# motor_shield__SD_v1_1_-_Ryan.net
KiCad netlist of a schematic drawn in EAGLE
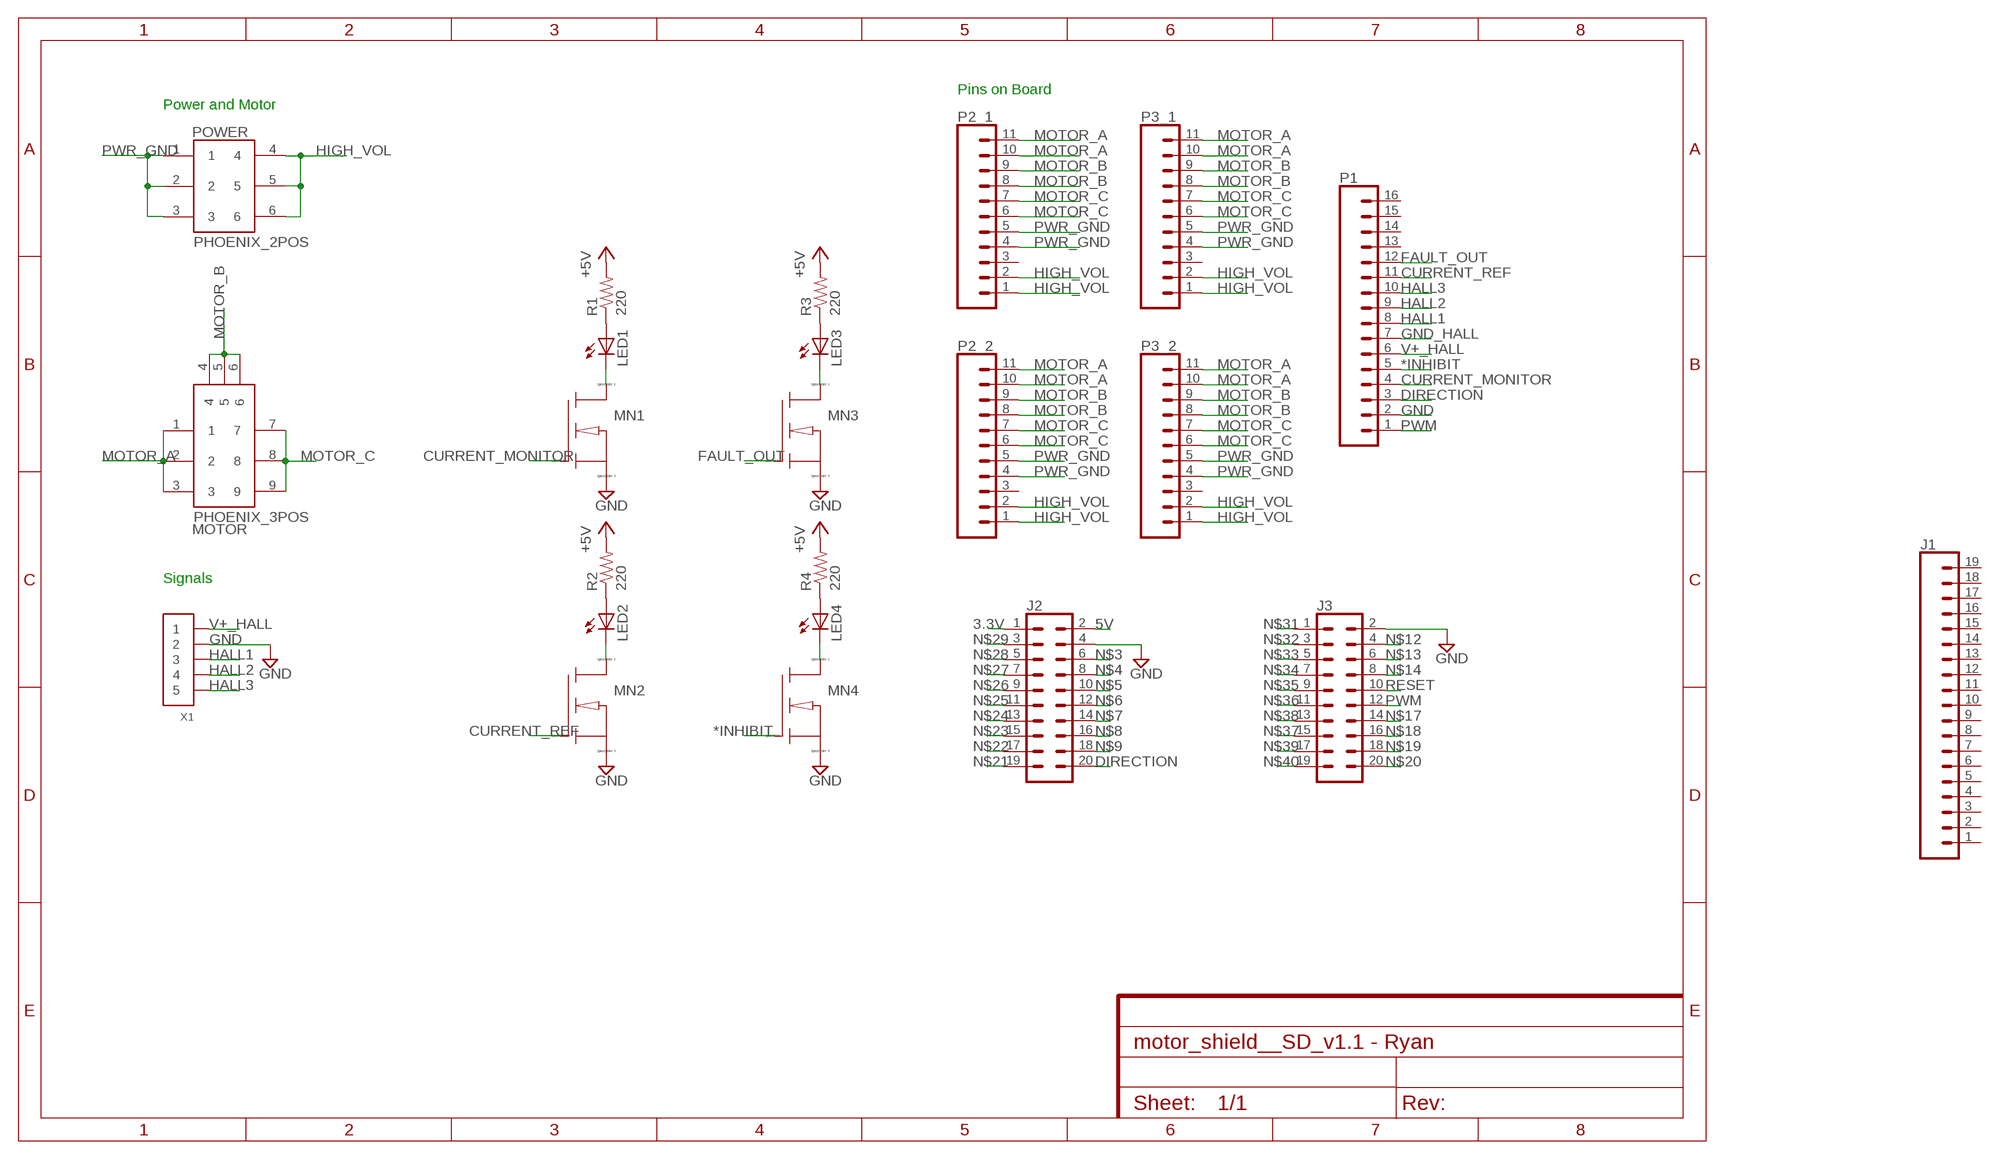
[diagram p0: schematic, sheet 1]

(export (version "E")
  (design (tool "Eeschema 10.0.6"))
  (components
    (comp (ref "J1")
      (value "CONN_19")
      (footprint "eagle-import:1X19")
      (libsource (lib "eagle-import") (part "CONN_19"))
    )
    (comp (ref "J2")
      (value "CONN_10X2")
      (footprint "eagle-import:2X10")
      (libsource (lib "eagle-import") (part "CONN_10X2"))
    )
    (comp (ref "J3")
      (value "CONN_10X2")
      (footprint "eagle-import:2X10")
      (libsource (lib "eagle-import") (part "CONN_10X2"))
    )
    (comp (ref "LED1")
      (value "LEDCHIPLED_0805")
      (footprint "eagle-import:CHIPLED_0805")
      (libsource (lib "eagle-import") (part "LEDCHIPLED_0805"))
    )
    (comp (ref "LED2")
      (value "LEDCHIPLED_0805")
      (footprint "eagle-import:CHIPLED_0805")
      (libsource (lib "eagle-import") (part "LEDCHIPLED_0805"))
    )
    (comp (ref "LED3")
      (value "LEDCHIPLED_0805")
      (footprint "eagle-import:CHIPLED_0805")
      (libsource (lib "eagle-import") (part "LEDCHIPLED_0805"))
    )
    (comp (ref "LED4")
      (value "LEDCHIPLED_0805")
      (footprint "eagle-import:CHIPLED_0805")
      (libsource (lib "eagle-import") (part "LEDCHIPLED_0805"))
    )
    (comp (ref "MN1")
      (value "NMOS")
      (footprint "eagle-import:SOT23")
      (libsource (lib "eagle-import") (part "NMOS"))
    )
    (comp (ref "MN2")
      (value "NMOS")
      (footprint "eagle-import:SOT23")
      (libsource (lib "eagle-import") (part "NMOS"))
    )
    (comp (ref "MN3")
      (value "NMOS")
      (footprint "eagle-import:SOT23")
      (libsource (lib "eagle-import") (part "NMOS"))
    )
    (comp (ref "MN4")
      (value "NMOS")
      (footprint "eagle-import:SOT23")
      (libsource (lib "eagle-import") (part "NMOS"))
    )
    (comp (ref "MOTOR")
      (value "PHOENIX_3POS")
      (footprint "eagle-import:PHOENIX_3POS")
      (libsource (lib "eagle-import") (part "PHOENIX_3POS"))
    )
    (comp (ref "P1")
      (value "CONN_16LOCK")
      (footprint "eagle-import:1X16_LOCK")
      (libsource (lib "eagle-import") (part "CONN_16LOCK"))
    )
    (comp (ref "P2_1")
      (value "CONN_11")
      (footprint "eagle-import:1X11")
      (libsource (lib "eagle-import") (part "CONN_11"))
    )
    (comp (ref "P2_2")
      (value "CONN_11")
      (footprint "eagle-import:1X11")
      (libsource (lib "eagle-import") (part "CONN_11"))
    )
    (comp (ref "P3_1")
      (value "CONN_11")
      (footprint "eagle-import:1X11")
      (libsource (lib "eagle-import") (part "CONN_11"))
    )
    (comp (ref "P3_2")
      (value "CONN_11")
      (footprint "eagle-import:1X11")
      (libsource (lib "eagle-import") (part "CONN_11"))
    )
    (comp (ref "POWER")
      (value "PHOENIX_2POS")
      (footprint "eagle-import:PHOENIX_2POS")
      (libsource (lib "eagle-import") (part "PHOENIX_2POS"))
    )
    (comp (ref "R1")
      (value "220")
      (footprint "eagle-import:R0603")
      (libsource (lib "eagle-import") (part "R-US_R0603"))
    )
    (comp (ref "R2")
      (value "220")
      (footprint "eagle-import:R0603")
      (libsource (lib "eagle-import") (part "R-US_R0603"))
    )
    (comp (ref "R3")
      (value "220")
      (footprint "eagle-import:R0603")
      (libsource (lib "eagle-import") (part "R-US_R0603"))
    )
    (comp (ref "R4")
      (value "220")
      (footprint "eagle-import:R0603")
      (libsource (lib "eagle-import") (part "R-US_R0603"))
    )
    (comp (ref "X1")
      (value "CONN_5-1-53261")
      (footprint "eagle-import:PB-53261-05")
      (libsource (lib "eagle-import") (part "CONN_5-1-53261"))
    )
  )
  (nets
    (net (code "1") (name "+5V") (class "Default")
      (node (ref "R1") (pin "2") (pinfunction "2_2") (pintype "passive"))
      (node (ref "R2") (pin "2") (pinfunction "2_2") (pintype "passive"))
      (node (ref "R3") (pin "2") (pinfunction "2_2") (pintype "passive"))
      (node (ref "R4") (pin "2") (pinfunction "2_2") (pintype "passive"))
    )
    (net (code "2") (name "/*INHIBIT") (class "Default")
      (node (ref "MN4") (pin "1") (pinfunction "G_1") (pintype "passive"))
      (node (ref "P1") (pin "5") (pinfunction "5_5") (pintype "passive"))
    )
    (net (code "3") (name "/3.3V") (class "Default")
      (node (ref "J2") (pin "1") (pinfunction "1_1") (pintype "passive"))
    )
    (net (code "4") (name "/5V") (class "Default")
      (node (ref "J2") (pin "2") (pinfunction "2_2") (pintype "passive"))
    )
    (net (code "5") (name "/CURRENT_MONITOR") (class "Default")
      (node (ref "MN1") (pin "1") (pinfunction "G_1") (pintype "passive"))
      (node (ref "P1") (pin "4") (pinfunction "4_4") (pintype "passive"))
    )
    (net (code "6") (name "/CURRENT_REF") (class "Default")
      (node (ref "MN2") (pin "1") (pinfunction "G_1") (pintype "passive"))
      (node (ref "P1") (pin "11") (pinfunction "11_11") (pintype "passive"))
    )
    (net (code "7") (name "/DIRECTION") (class "Default")
      (node (ref "J2") (pin "20") (pinfunction "20_20") (pintype "passive"))
      (node (ref "P1") (pin "3") (pinfunction "3_3") (pintype "passive"))
    )
    (net (code "8") (name "/FAULT_OUT") (class "Default")
      (node (ref "MN3") (pin "1") (pinfunction "G_1") (pintype "passive"))
      (node (ref "P1") (pin "12") (pinfunction "12_12") (pintype "passive"))
    )
    (net (code "9") (name "/GND_HALL") (class "Default")
      (node (ref "P1") (pin "7") (pinfunction "7_7") (pintype "passive"))
    )
    (net (code "10") (name "/HALL1") (class "Default")
      (node (ref "P1") (pin "8") (pinfunction "8_8") (pintype "passive"))
      (node (ref "X1") (pin "3") (pinfunction "3_3") (pintype "bidirectional"))
    )
    (net (code "11") (name "/HALL2") (class "Default")
      (node (ref "P1") (pin "9") (pinfunction "9_9") (pintype "passive"))
      (node (ref "X1") (pin "4") (pinfunction "4_4") (pintype "bidirectional"))
    )
    (net (code "12") (name "/HALL3") (class "Default")
      (node (ref "P1") (pin "10") (pinfunction "10_10") (pintype "passive"))
      (node (ref "X1") (pin "5") (pinfunction "5_5") (pintype "bidirectional"))
    )
    (net (code "13") (name "/HIGH_VOL") (class "Default")
      (node (ref "P2_1") (pin "1") (pinfunction "1_1") (pintype "passive"))
      (node (ref "P2_1") (pin "2") (pinfunction "2_2") (pintype "passive"))
      (node (ref "P2_2") (pin "1") (pinfunction "1_1") (pintype "passive"))
      (node (ref "P2_2") (pin "2") (pinfunction "2_2") (pintype "passive"))
      (node (ref "P3_1") (pin "1") (pinfunction "1_1") (pintype "passive"))
      (node (ref "P3_1") (pin "2") (pinfunction "2_2") (pintype "passive"))
      (node (ref "P3_2") (pin "1") (pinfunction "1_1") (pintype "passive"))
      (node (ref "P3_2") (pin "2") (pinfunction "2_2") (pintype "passive"))
      (node (ref "POWER") (pin "4") (pinfunction "4_4") (pintype "bidirectional"))
      (node (ref "POWER") (pin "5") (pinfunction "5_5") (pintype "bidirectional"))
      (node (ref "POWER") (pin "6") (pinfunction "6_6") (pintype "bidirectional"))
    )
    (net (code "14") (name "/MOTOR_A") (class "Default")
      (node (ref "MOTOR") (pin "1") (pinfunction "1_1") (pintype "bidirectional"))
      (node (ref "MOTOR") (pin "2") (pinfunction "2_2") (pintype "bidirectional"))
      (node (ref "MOTOR") (pin "3") (pinfunction "3_3") (pintype "bidirectional"))
      (node (ref "P2_1") (pin "10") (pinfunction "10_10") (pintype "passive"))
      (node (ref "P2_1") (pin "11") (pinfunction "11_11") (pintype "passive"))
      (node (ref "P2_2") (pin "10") (pinfunction "10_10") (pintype "passive"))
      (node (ref "P2_2") (pin "11") (pinfunction "11_11") (pintype "passive"))
      (node (ref "P3_1") (pin "10") (pinfunction "10_10") (pintype "passive"))
      (node (ref "P3_1") (pin "11") (pinfunction "11_11") (pintype "passive"))
      (node (ref "P3_2") (pin "10") (pinfunction "10_10") (pintype "passive"))
      (node (ref "P3_2") (pin "11") (pinfunction "11_11") (pintype "passive"))
    )
    (net (code "15") (name "/MOTOR_B") (class "Default")
      (node (ref "MOTOR") (pin "4") (pinfunction "4_4") (pintype "bidirectional"))
      (node (ref "MOTOR") (pin "5") (pinfunction "5_5") (pintype "bidirectional"))
      (node (ref "MOTOR") (pin "6") (pinfunction "6_6") (pintype "bidirectional"))
      (node (ref "P2_1") (pin "8") (pinfunction "8_8") (pintype "passive"))
      (node (ref "P2_1") (pin "9") (pinfunction "9_9") (pintype "passive"))
      (node (ref "P2_2") (pin "8") (pinfunction "8_8") (pintype "passive"))
      (node (ref "P2_2") (pin "9") (pinfunction "9_9") (pintype "passive"))
      (node (ref "P3_1") (pin "8") (pinfunction "8_8") (pintype "passive"))
      (node (ref "P3_1") (pin "9") (pinfunction "9_9") (pintype "passive"))
      (node (ref "P3_2") (pin "8") (pinfunction "8_8") (pintype "passive"))
      (node (ref "P3_2") (pin "9") (pinfunction "9_9") (pintype "passive"))
    )
    (net (code "16") (name "/MOTOR_C") (class "Default")
      (node (ref "MOTOR") (pin "7") (pinfunction "7_7") (pintype "bidirectional"))
      (node (ref "MOTOR") (pin "8") (pinfunction "8_8") (pintype "bidirectional"))
      (node (ref "MOTOR") (pin "9") (pinfunction "9_9") (pintype "bidirectional"))
      (node (ref "P2_1") (pin "6") (pinfunction "6_6") (pintype "passive"))
      (node (ref "P2_1") (pin "7") (pinfunction "7_7") (pintype "passive"))
      (node (ref "P2_2") (pin "6") (pinfunction "6_6") (pintype "passive"))
      (node (ref "P2_2") (pin "7") (pinfunction "7_7") (pintype "passive"))
      (node (ref "P3_1") (pin "6") (pinfunction "6_6") (pintype "passive"))
      (node (ref "P3_1") (pin "7") (pinfunction "7_7") (pintype "passive"))
      (node (ref "P3_2") (pin "6") (pinfunction "6_6") (pintype "passive"))
      (node (ref "P3_2") (pin "7") (pinfunction "7_7") (pintype "passive"))
    )
    (net (code "17") (name "/N$3") (class "Default")
      (node (ref "J2") (pin "6") (pinfunction "6_6") (pintype "passive"))
    )
    (net (code "18") (name "/N$4") (class "Default")
      (node (ref "J2") (pin "8") (pinfunction "8_8") (pintype "passive"))
    )
    (net (code "19") (name "/N$5") (class "Default")
      (node (ref "J2") (pin "10") (pinfunction "10_10") (pintype "passive"))
    )
    (net (code "20") (name "/N$6") (class "Default")
      (node (ref "J2") (pin "12") (pinfunction "12_12") (pintype "passive"))
    )
    (net (code "21") (name "/N$7") (class "Default")
      (node (ref "J2") (pin "14") (pinfunction "14_14") (pintype "passive"))
    )
    (net (code "22") (name "/N$8") (class "Default")
      (node (ref "J2") (pin "16") (pinfunction "16_16") (pintype "passive"))
    )
    (net (code "23") (name "/N$9") (class "Default")
      (node (ref "J2") (pin "18") (pinfunction "18_18") (pintype "passive"))
    )
    (net (code "24") (name "/N$12") (class "Default")
      (node (ref "J3") (pin "4") (pinfunction "4_4") (pintype "passive"))
    )
    (net (code "25") (name "/N$13") (class "Default")
      (node (ref "J3") (pin "6") (pinfunction "6_6") (pintype "passive"))
    )
    (net (code "26") (name "/N$14") (class "Default")
      (node (ref "J3") (pin "8") (pinfunction "8_8") (pintype "passive"))
    )
    (net (code "27") (name "/N$17") (class "Default")
      (node (ref "J3") (pin "14") (pinfunction "14_14") (pintype "passive"))
    )
    (net (code "28") (name "/N$18") (class "Default")
      (node (ref "J3") (pin "16") (pinfunction "16_16") (pintype "passive"))
    )
    (net (code "29") (name "/N$19") (class "Default")
      (node (ref "J3") (pin "18") (pinfunction "18_18") (pintype "passive"))
    )
    (net (code "30") (name "/N$20") (class "Default")
      (node (ref "J3") (pin "20") (pinfunction "20_20") (pintype "passive"))
    )
    (net (code "31") (name "/N$21") (class "Default")
      (node (ref "J2") (pin "19") (pinfunction "19_19") (pintype "passive"))
    )
    (net (code "32") (name "/N$22") (class "Default")
      (node (ref "J2") (pin "17") (pinfunction "17_17") (pintype "passive"))
    )
    (net (code "33") (name "/N$23") (class "Default")
      (node (ref "J2") (pin "15") (pinfunction "15_15") (pintype "passive"))
    )
    (net (code "34") (name "/N$24") (class "Default")
      (node (ref "J2") (pin "13") (pinfunction "13_13") (pintype "passive"))
    )
    (net (code "35") (name "/N$25") (class "Default")
      (node (ref "J2") (pin "11") (pinfunction "11_11") (pintype "passive"))
    )
    (net (code "36") (name "/N$26") (class "Default")
      (node (ref "J2") (pin "9") (pinfunction "9_9") (pintype "passive"))
    )
    (net (code "37") (name "/N$27") (class "Default")
      (node (ref "J2") (pin "7") (pinfunction "7_7") (pintype "passive"))
    )
    (net (code "38") (name "/N$28") (class "Default")
      (node (ref "J2") (pin "5") (pinfunction "5_5") (pintype "passive"))
    )
    (net (code "39") (name "/N$29") (class "Default")
      (node (ref "J2") (pin "3") (pinfunction "3_3") (pintype "passive"))
    )
    (net (code "40") (name "/N$31") (class "Default")
      (node (ref "J3") (pin "1") (pinfunction "1_1") (pintype "passive"))
    )
    (net (code "41") (name "/N$32") (class "Default")
      (node (ref "J3") (pin "3") (pinfunction "3_3") (pintype "passive"))
    )
    (net (code "42") (name "/N$33") (class "Default")
      (node (ref "J3") (pin "5") (pinfunction "5_5") (pintype "passive"))
    )
    (net (code "43") (name "/N$34") (class "Default")
      (node (ref "J3") (pin "7") (pinfunction "7_7") (pintype "passive"))
    )
    (net (code "44") (name "/N$35") (class "Default")
      (node (ref "J3") (pin "9") (pinfunction "9_9") (pintype "passive"))
    )
    (net (code "45") (name "/N$36") (class "Default")
      (node (ref "J3") (pin "11") (pinfunction "11_11") (pintype "passive"))
    )
    (net (code "46") (name "/N$37") (class "Default")
      (node (ref "J3") (pin "15") (pinfunction "15_15") (pintype "passive"))
    )
    (net (code "47") (name "/N$38") (class "Default")
      (node (ref "J3") (pin "13") (pinfunction "13_13") (pintype "passive"))
    )
    (net (code "48") (name "/N$39") (class "Default")
      (node (ref "J3") (pin "17") (pinfunction "17_17") (pintype "passive"))
    )
    (net (code "49") (name "/N$40") (class "Default")
      (node (ref "J3") (pin "19") (pinfunction "19_19") (pintype "passive"))
    )
    (net (code "50") (name "/PWM") (class "Default")
      (node (ref "J3") (pin "12") (pinfunction "12_12") (pintype "passive"))
      (node (ref "P1") (pin "1") (pinfunction "1_1") (pintype "passive"))
    )
    (net (code "51") (name "/PWR_GND") (class "Default")
      (node (ref "P2_1") (pin "4") (pinfunction "4_4") (pintype "passive"))
      (node (ref "P2_1") (pin "5") (pinfunction "5_5") (pintype "passive"))
      (node (ref "P2_2") (pin "4") (pinfunction "4_4") (pintype "passive"))
      (node (ref "P2_2") (pin "5") (pinfunction "5_5") (pintype "passive"))
      (node (ref "P3_1") (pin "4") (pinfunction "4_4") (pintype "passive"))
      (node (ref "P3_1") (pin "5") (pinfunction "5_5") (pintype "passive"))
      (node (ref "P3_2") (pin "4") (pinfunction "4_4") (pintype "passive"))
      (node (ref "P3_2") (pin "5") (pinfunction "5_5") (pintype "passive"))
      (node (ref "POWER") (pin "1") (pinfunction "1_1") (pintype "bidirectional"))
      (node (ref "POWER") (pin "2") (pinfunction "2_2") (pintype "bidirectional"))
      (node (ref "POWER") (pin "3") (pinfunction "3_3") (pintype "bidirectional"))
    )
    (net (code "52") (name "/RESET") (class "Default")
      (node (ref "J3") (pin "10") (pinfunction "10_10") (pintype "passive"))
    )
    (net (code "53") (name "/V+_HALL") (class "Default")
      (node (ref "P1") (pin "6") (pinfunction "6_6") (pintype "passive"))
      (node (ref "X1") (pin "1") (pinfunction "1_1") (pintype "bidirectional"))
    )
    (net (code "54") (name "GND") (class "Default")
      (node (ref "J2") (pin "4") (pinfunction "4_4") (pintype "passive"))
      (node (ref "J3") (pin "2") (pinfunction "2_2") (pintype "passive"))
      (node (ref "MN1") (pin "2") (pinfunction "S_2") (pintype "passive"))
      (node (ref "MN2") (pin "2") (pinfunction "S_2") (pintype "passive"))
      (node (ref "MN3") (pin "2") (pinfunction "S_2") (pintype "passive"))
      (node (ref "MN4") (pin "2") (pinfunction "S_2") (pintype "passive"))
      (node (ref "P1") (pin "2") (pinfunction "2_2") (pintype "passive"))
      (node (ref "X1") (pin "2") (pinfunction "2_2") (pintype "bidirectional"))
    )
    (net (code "55") (name "Net-(LED1-PadA)") (class "Default")
      (node (ref "LED1") (pin "A") (pinfunction "A_A") (pintype "passive"))
      (node (ref "R1") (pin "1") (pinfunction "1_1") (pintype "passive"))
    )
    (net (code "56") (name "Net-(LED2-PadA)") (class "Default")
      (node (ref "LED2") (pin "A") (pinfunction "A_A") (pintype "passive"))
      (node (ref "R2") (pin "1") (pinfunction "1_1") (pintype "passive"))
    )
    (net (code "57") (name "Net-(LED3-PadA)") (class "Default")
      (node (ref "LED3") (pin "A") (pinfunction "A_A") (pintype "passive"))
      (node (ref "R3") (pin "1") (pinfunction "1_1") (pintype "passive"))
    )
    (net (code "58") (name "Net-(LED4-PadA)") (class "Default")
      (node (ref "LED4") (pin "A") (pinfunction "A_A") (pintype "passive"))
      (node (ref "R4") (pin "1") (pinfunction "1_1") (pintype "passive"))
    )
    (net (code "59") (name "Net-(MN1-D)") (class "Default")
      (node (ref "LED1") (pin "C") (pinfunction "C_C") (pintype "passive"))
      (node (ref "MN1") (pin "3") (pinfunction "D_3") (pintype "passive"))
    )
    (net (code "60") (name "Net-(MN2-D)") (class "Default")
      (node (ref "LED2") (pin "C") (pinfunction "C_C") (pintype "passive"))
      (node (ref "MN2") (pin "3") (pinfunction "D_3") (pintype "passive"))
    )
    (net (code "61") (name "Net-(MN3-D)") (class "Default")
      (node (ref "LED3") (pin "C") (pinfunction "C_C") (pintype "passive"))
      (node (ref "MN3") (pin "3") (pinfunction "D_3") (pintype "passive"))
    )
    (net (code "62") (name "Net-(MN4-D)") (class "Default")
      (node (ref "LED4") (pin "C") (pinfunction "C_C") (pintype "passive"))
      (node (ref "MN4") (pin "3") (pinfunction "D_3") (pintype "passive"))
    )
    (net (code "63") (name "unconnected-(J1-Pad1)") (class "Default")
      (node (ref "J1") (pin "1") (pinfunction "1_1") (pintype "passive"))
    )
    (net (code "64") (name "unconnected-(J1-Pad2)") (class "Default")
      (node (ref "J1") (pin "2") (pinfunction "2_2") (pintype "passive"))
    )
    (net (code "65") (name "unconnected-(J1-Pad3)") (class "Default")
      (node (ref "J1") (pin "3") (pinfunction "3_3") (pintype "passive"))
    )
    (net (code "66") (name "unconnected-(J1-Pad4)") (class "Default")
      (node (ref "J1") (pin "4") (pinfunction "4_4") (pintype "passive"))
    )
    (net (code "67") (name "unconnected-(J1-Pad5)") (class "Default")
      (node (ref "J1") (pin "5") (pinfunction "5_5") (pintype "passive"))
    )
    (net (code "68") (name "unconnected-(J1-Pad6)") (class "Default")
      (node (ref "J1") (pin "6") (pinfunction "6_6") (pintype "passive"))
    )
    (net (code "69") (name "unconnected-(J1-Pad7)") (class "Default")
      (node (ref "J1") (pin "7") (pinfunction "7_7") (pintype "passive"))
    )
    (net (code "70") (name "unconnected-(J1-Pad8)") (class "Default")
      (node (ref "J1") (pin "8") (pinfunction "8_8") (pintype "passive"))
    )
    (net (code "71") (name "unconnected-(J1-Pad9)") (class "Default")
      (node (ref "J1") (pin "9") (pinfunction "9_9") (pintype "passive"))
    )
    (net (code "72") (name "unconnected-(J1-Pad10)") (class "Default")
      (node (ref "J1") (pin "10") (pinfunction "10_10") (pintype "passive"))
    )
    (net (code "73") (name "unconnected-(J1-Pad11)") (class "Default")
      (node (ref "J1") (pin "11") (pinfunction "11_11") (pintype "passive"))
    )
    (net (code "74") (name "unconnected-(J1-Pad12)") (class "Default")
      (node (ref "J1") (pin "12") (pinfunction "12_12") (pintype "passive"))
    )
    (net (code "75") (name "unconnected-(J1-Pad13)") (class "Default")
      (node (ref "J1") (pin "13") (pinfunction "13_13") (pintype "passive"))
    )
    (net (code "76") (name "unconnected-(J1-Pad14)") (class "Default")
      (node (ref "J1") (pin "14") (pinfunction "14_14") (pintype "passive"))
    )
    (net (code "77") (name "unconnected-(J1-Pad15)") (class "Default")
      (node (ref "J1") (pin "15") (pinfunction "15_15") (pintype "passive"))
    )
    (net (code "78") (name "unconnected-(J1-Pad16)") (class "Default")
      (node (ref "J1") (pin "16") (pinfunction "16_16") (pintype "passive"))
    )
    (net (code "79") (name "unconnected-(J1-Pad17)") (class "Default")
      (node (ref "J1") (pin "17") (pinfunction "17_17") (pintype "passive"))
    )
    (net (code "80") (name "unconnected-(J1-Pad18)") (class "Default")
      (node (ref "J1") (pin "18") (pinfunction "18_18") (pintype "passive"))
    )
    (net (code "81") (name "unconnected-(J1-Pad19)") (class "Default")
      (node (ref "J1") (pin "19") (pinfunction "19_19") (pintype "passive"))
    )
    (net (code "82") (name "unconnected-(P1-Pad13)") (class "Default")
      (node (ref "P1") (pin "13") (pinfunction "13_13") (pintype "passive"))
    )
    (net (code "83") (name "unconnected-(P1-Pad14)") (class "Default")
      (node (ref "P1") (pin "14") (pinfunction "14_14") (pintype "passive"))
    )
    (net (code "84") (name "unconnected-(P1-Pad15)") (class "Default")
      (node (ref "P1") (pin "15") (pinfunction "15_15") (pintype "passive"))
    )
    (net (code "85") (name "unconnected-(P1-Pad16)") (class "Default")
      (node (ref "P1") (pin "16") (pinfunction "16_16") (pintype "passive"))
    )
    (net (code "86") (name "unconnected-(P2_1-Pad3)") (class "Default")
      (node (ref "P2_1") (pin "3") (pinfunction "3_3") (pintype "passive"))
    )
    (net (code "87") (name "unconnected-(P2_2-Pad3)") (class "Default")
      (node (ref "P2_2") (pin "3") (pinfunction "3_3") (pintype "passive"))
    )
    (net (code "88") (name "unconnected-(P3_1-Pad3)") (class "Default")
      (node (ref "P3_1") (pin "3") (pinfunction "3_3") (pintype "passive"))
    )
    (net (code "89") (name "unconnected-(P3_2-Pad3)") (class "Default")
      (node (ref "P3_2") (pin "3") (pinfunction "3_3") (pintype "passive"))
    )
  )
)
